# ET312.net
KiCad netlist of a schematic drawn in EAGLE
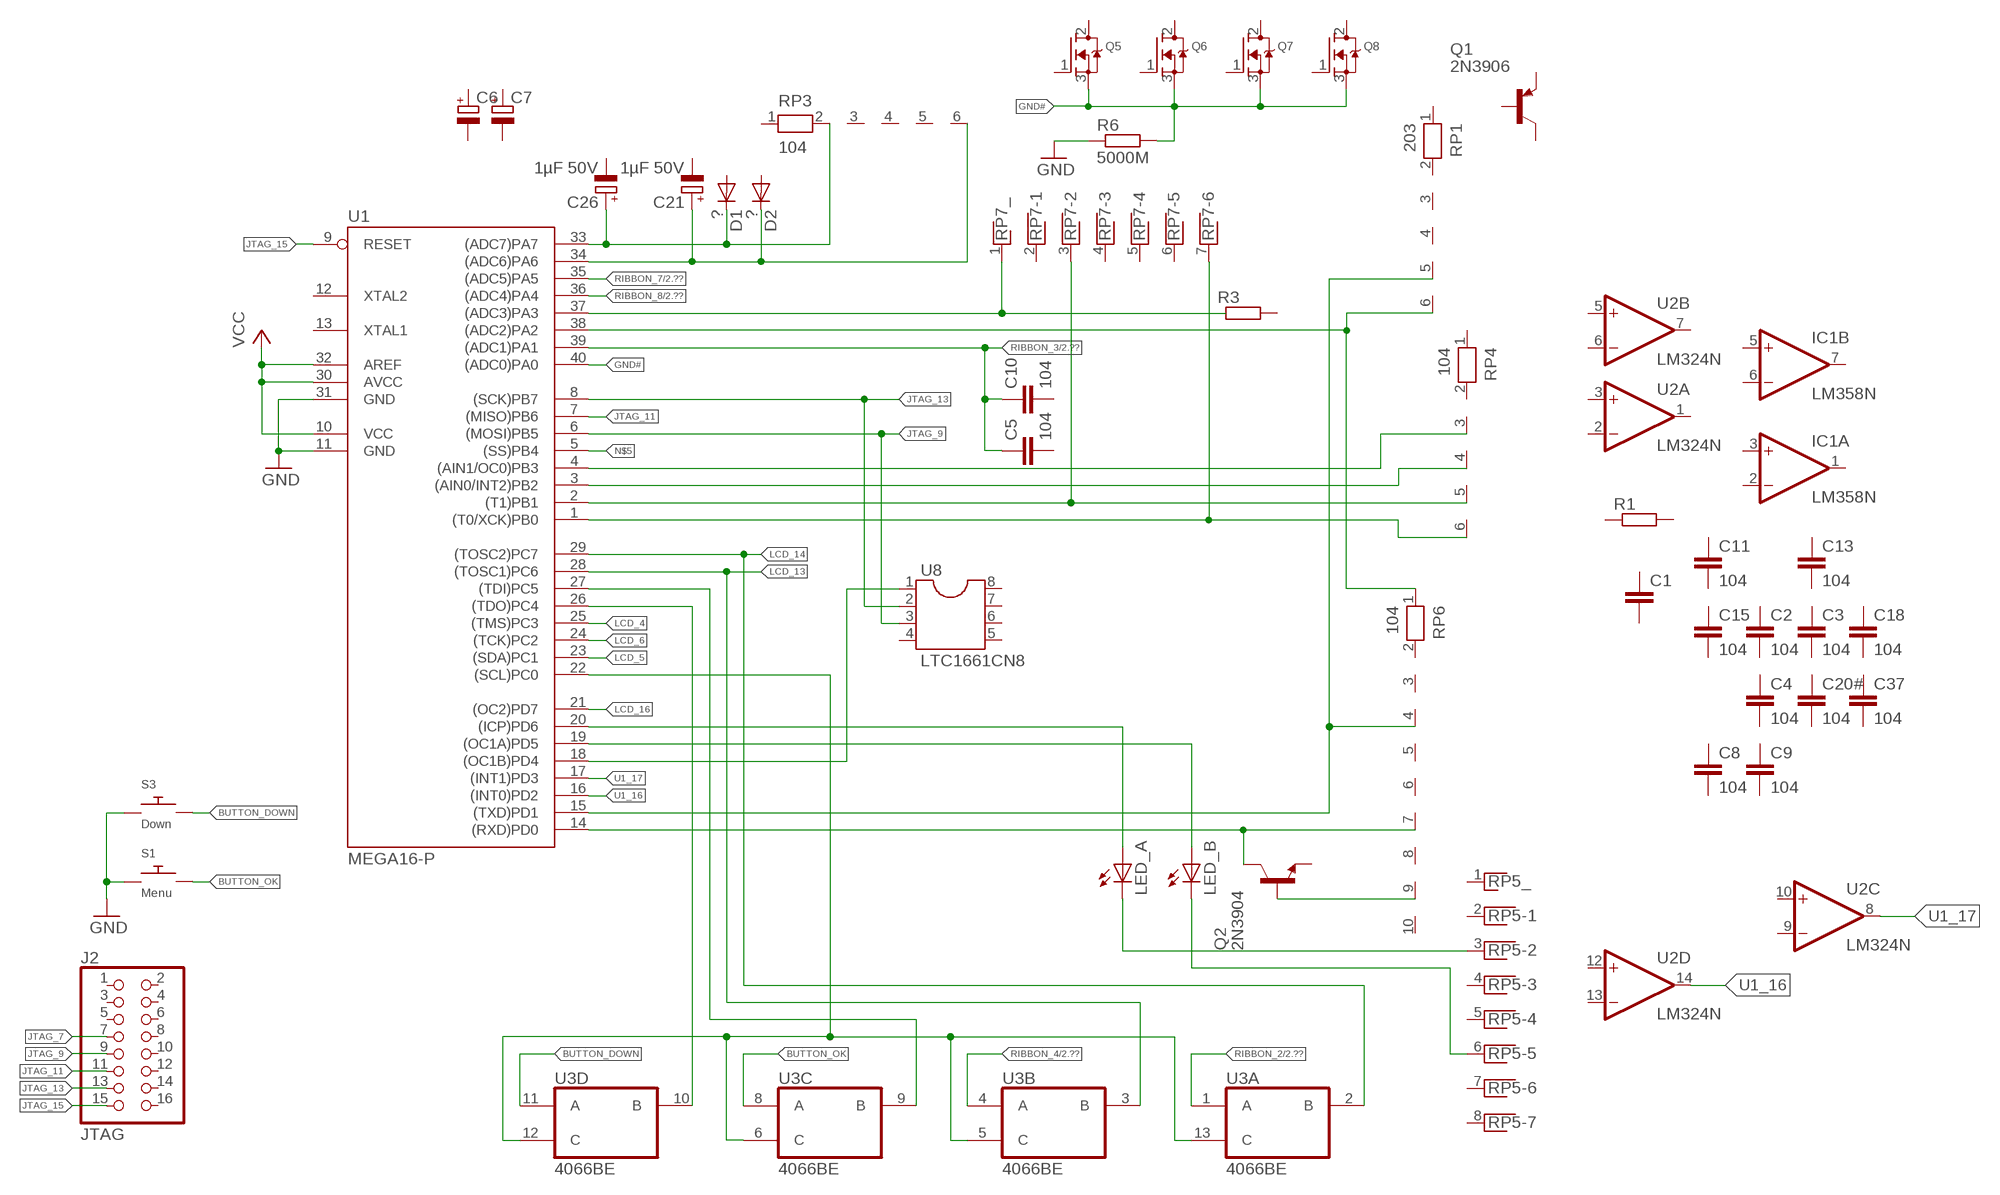
[diagram p0: schematic, sheet 1]
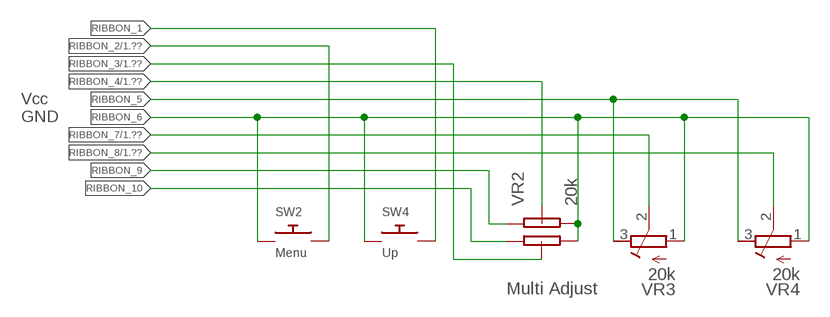
[diagram p1: schematic, sheet 2]

(export (version "E")
  (design (tool "Eeschema 10.0.6"))
  (components
    (comp (ref "SW2")
      (value "Menu")
      (footprint "eagle-import:TACT_PANA-EVQ")
      (libsource (lib "eagle-import") (part "SWITCH_PUSHBUTTONEVQ-PE"))
    )
    (comp (ref "SW4")
      (value "Up")
      (footprint "eagle-import:TACT_PANA-EVQ")
      (libsource (lib "eagle-import") (part "SWITCH_PUSHBUTTONEVQ-PE"))
    )
    (comp (ref "VR2")
      (value "20k")
      (footprint "eagle-import:EVJC")
      (libsource (lib "eagle-import") (part "EVJC"))
    )
    (comp (ref "VR3")
      (value "20k")
      (footprint "eagle-import:RTRIM64W")
      (libsource (lib "eagle-import") (part "R-TRIMM64W"))
    )
    (comp (ref "VR4")
      (value "20k")
      (footprint "eagle-import:RTRIM64W")
      (libsource (lib "eagle-import") (part "R-TRIMM64W"))
    )
    (comp (ref "C1")
      (value "C-EU025-025X050")
      (footprint "eagle-import:C025-025X050")
      (libsource (lib "eagle-import") (part "resistor_C-EU025-025X050"))
    )
    (comp (ref "C2")
      (value "104")
      (footprint "eagle-import:C025-024X044")
      (libsource (lib "eagle-import") (part "C-EU025-024X044"))
    )
    (comp (ref "C3")
      (value "104")
      (footprint "eagle-import:C025-024X044")
      (libsource (lib "eagle-import") (part "C-EU025-024X044"))
    )
    (comp (ref "C4")
      (value "104")
      (footprint "eagle-import:C025-024X044")
      (libsource (lib "eagle-import") (part "C-EU025-024X044"))
    )
    (comp (ref "C5")
      (value "104")
      (footprint "eagle-import:C025-024X044")
      (libsource (lib "eagle-import") (part "C-EU025-024X044"))
    )
    (comp (ref "C6")
      (value "CPOL-EUE2-5")
      (footprint "eagle-import:E2-5")
      (libsource (lib "eagle-import") (part "CPOL-EUE2-5"))
    )
    (comp (ref "C7")
      (value "CPOL-EUE2-5")
      (footprint "eagle-import:E2-5")
      (libsource (lib "eagle-import") (part "CPOL-EUE2-5"))
    )
    (comp (ref "C8")
      (value "104")
      (footprint "eagle-import:C025-024X044")
      (libsource (lib "eagle-import") (part "C-EU025-024X044"))
    )
    (comp (ref "C9")
      (value "104")
      (footprint "eagle-import:C025-024X044")
      (libsource (lib "eagle-import") (part "C-EU025-024X044"))
    )
    (comp (ref "C10")
      (value "104")
      (footprint "eagle-import:C025-024X044")
      (libsource (lib "eagle-import") (part "C-EU025-024X044"))
    )
    (comp (ref "C11")
      (value "104")
      (footprint "eagle-import:C025-024X044")
      (libsource (lib "eagle-import") (part "C-EU025-024X044"))
    )
    (comp (ref "C13")
      (value "104")
      (footprint "eagle-import:C025-024X044")
      (libsource (lib "eagle-import") (part "C-EU025-024X044"))
    )
    (comp (ref "C15")
      (value "104")
      (footprint "eagle-import:C025-024X044")
      (libsource (lib "eagle-import") (part "C-EU025-024X044"))
    )
    (comp (ref "C18")
      (value "104")
      (footprint "eagle-import:C025-024X044")
      (libsource (lib "eagle-import") (part "C-EU025-024X044"))
    )
    (comp (ref "C20#")
      (value "104")
      (footprint "eagle-import:C025-024X044")
      (libsource (lib "eagle-import") (part "C-EU025-024X044"))
    )
    (comp (ref "C21")
      (value "1µF 50V")
      (footprint "eagle-import:E2-5")
      (libsource (lib "eagle-import") (part "CPOL-EUE2-5"))
    )
    (comp (ref "C26")
      (value "1µF 50V")
      (footprint "eagle-import:E2-5")
      (libsource (lib "eagle-import") (part "CPOL-EUE2-5"))
    )
    (comp (ref "C37")
      (value "104")
      (footprint "eagle-import:C025-024X044")
      (libsource (lib "eagle-import") (part "C-EU025-024X044"))
    )
    (comp (ref "D1")
      (value "?")
      (footprint "eagle-import:DO41-10")
      (libsource (lib "eagle-import") (part "1N4004"))
    )
    (comp (ref "D2")
      (value "?")
      (footprint "eagle-import:DO41-10")
      (libsource (lib "eagle-import") (part "1N4004"))
    )
    (comp (ref "IC1")
      (value "LM358N")
      (footprint "eagle-import:DIL08")
      (libsource (lib "eagle-import") (part "LM358N"))
    )
    (comp (ref "J2")
      (value "JTAG")
      (footprint "eagle-import:2X08")
      (libsource (lib "eagle-import") (part "PINHD-2X8"))
    )
    (comp (ref "LED_A")
      (value "LEDB155")
      (footprint "eagle-import:Q62902-B155")
      (libsource (lib "eagle-import") (part "LEDB155"))
    )
    (comp (ref "LED_B")
      (value "LEDB155")
      (footprint "eagle-import:Q62902-B155")
      (libsource (lib "eagle-import") (part "LEDB155"))
    )
    (comp (ref "Q1")
      (value "2N3906")
      (footprint "eagle-import:TO92")
      (libsource (lib "eagle-import") (part "2N3906"))
    )
    (comp (ref "Q2")
      (value "2N3904")
      (footprint "eagle-import:TO92")
      (libsource (lib "eagle-import") (part "2N3904"))
    )
    (comp (ref "Q5")
      (value "MOSFET-NGDS_TO220V")
      (footprint "eagle-import:TO220V")
      (libsource (lib "eagle-import") (part "MOSFET-NGDS_TO220V"))
    )
    (comp (ref "Q6")
      (value "MOSFET-NGDS_TO220V")
      (footprint "eagle-import:TO220V")
      (libsource (lib "eagle-import") (part "MOSFET-NGDS_TO220V"))
    )
    (comp (ref "Q7")
      (value "MOSFET-NGDS_TO220V")
      (footprint "eagle-import:TO220V")
      (libsource (lib "eagle-import") (part "MOSFET-NGDS_TO220V"))
    )
    (comp (ref "Q8")
      (value "MOSFET-NGDS_TO220V")
      (footprint "eagle-import:TO220V")
      (libsource (lib "eagle-import") (part "MOSFET-NGDS_TO220V"))
    )
    (comp (ref "R1")
      (value "R-EU_0207/5V")
      (footprint "eagle-import:0207_5V")
      (libsource (lib "eagle-import") (part "R-EU_0207/5V"))
    )
    (comp (ref "R3")
      (value "R-EU_0207/5V")
      (footprint "eagle-import:0207_5V")
      (libsource (lib "eagle-import") (part "R-EU_0207/5V"))
    )
    (comp (ref "R6")
      (value "5000M")
      (footprint "eagle-import:0207_5V")
      (libsource (lib "eagle-import") (part "R-EU_0207/5V"))
    )
    (comp (ref "RP1")
      (value "203")
      (footprint "eagle-import:RN-6")
      (libsource (lib "eagle-import") (part "RN05"))
    )
    (comp (ref "RP3")
      (value "104")
      (footprint "eagle-import:RN-6")
      (libsource (lib "eagle-import") (part "RN05"))
    )
    (comp (ref "RP4")
      (value "104")
      (footprint "eagle-import:RN-6")
      (libsource (lib "eagle-import") (part "RN05"))
    )
    (comp (ref "RP5")
      (value "RNX7")
      (footprint "eagle-import:RN-8")
      (libsource (lib "eagle-import") (part "RNX7"))
    )
    (comp (ref "RP6")
      (value "104")
      (footprint "eagle-import:RN-10")
      (libsource (lib "eagle-import") (part "RN09"))
    )
    (comp (ref "RP7")
      (value "RNX6")
      (footprint "eagle-import:RN-7")
      (libsource (lib "eagle-import") (part "RNX6"))
    )
    (comp (ref "S1")
      (value "Menu")
      (footprint "eagle-import:TACT_PANA-EVQ")
      (libsource (lib "eagle-import") (part "SWITCH_PUSHBUTTONEVQ-PE"))
    )
    (comp (ref "S3")
      (value "Down")
      (footprint "eagle-import:TACT_PANA-EVQ")
      (libsource (lib "eagle-import") (part "SWITCH_PUSHBUTTONEVQ-PE"))
    )
    (comp (ref "U1")
      (value "MEGA16-P")
      (footprint "eagle-import:DIL40")
      (fields (field (name "MPN") "ATMEGA16-16PU"))
      (libsource (lib "eagle-import") (part "MEGA16-P"))
    )
    (comp (ref "U2")
      (value "LM324N")
      (footprint "eagle-import:DIL14")
      (libsource (lib "eagle-import") (part "LM324N"))
    )
    (comp (ref "U3")
      (value "4066BE")
      (footprint "eagle-import:DIL14")
      (libsource (lib "eagle-import") (part "4066N"))
    )
    (comp (ref "U8")
      (value "LTC1661CN8")
      (footprint "eagle-import:DIL08")
      (libsource (lib "eagle-import") (part "DIL8"))
    )
  )
  (nets
    (net (code "1") (name "BUTTON_DOWN") (class "Default")
      (node (ref "S3") (pin "P$2") (pinfunction "P$2_P$2") (pintype "passive"))
      (node (ref "U3") (pin "11") (pinfunction "A_11") (pintype "tri_state"))
    )
    (net (code "2") (name "BUTTON_OK") (class "Default")
      (node (ref "S1") (pin "P$2") (pinfunction "P$2_P$2") (pintype "passive"))
      (node (ref "U3") (pin "8") (pinfunction "A_8") (pintype "tri_state"))
    )
    (net (code "3") (name "GND") (class "Default")
      (node (ref "R6") (pin "1") (pinfunction "1_1") (pintype "passive"))
      (node (ref "S1") (pin "P$1") (pinfunction "P$1_P$1") (pintype "passive"))
      (node (ref "S3") (pin "P$1") (pinfunction "P$1_P$1") (pintype "passive"))
      (node (ref "U1") (pin "11") (pinfunction "GND_11") (pintype "power_in"))
      (node (ref "U1") (pin "31") (pinfunction "GND_31") (pintype "power_in"))
    )
    (net (code "4") (name "GND#") (class "Default")
      (node (ref "Q5") (pin "3") (pinfunction "S_3") (pintype "bidirectional"))
      (node (ref "Q6") (pin "3") (pinfunction "S_3") (pintype "bidirectional"))
      (node (ref "Q7") (pin "3") (pinfunction "S_3") (pintype "bidirectional"))
      (node (ref "Q8") (pin "3") (pinfunction "S_3") (pintype "bidirectional"))
      (node (ref "R6") (pin "2") (pinfunction "2_2") (pintype "passive"))
      (node (ref "U1") (pin "40") (pinfunction "(ADC0)PA0_40") (pintype "bidirectional"))
    )
    (net (code "5") (name "JTAG_7") (class "Default")
      (node (ref "J2") (pin "7") (pinfunction "7_7") (pintype "passive"))
      (node (ref "RP4") (pin "3") (pinfunction "3_3") (pintype "passive"))
      (node (ref "U1") (pin "4") (pinfunction "(AIN1/OC0)PB3_4") (pintype "bidirectional"))
    )
    (net (code "6") (name "JTAG_9") (class "Default")
      (node (ref "J2") (pin "9") (pinfunction "9_9") (pintype "passive"))
      (node (ref "U1") (pin "6") (pinfunction "(MOSI)PB5_6") (pintype "bidirectional"))
      (node (ref "U8") (pin "3") (pinfunction "3_3") (pintype "passive"))
    )
    (net (code "7") (name "JTAG_11") (class "Default")
      (node (ref "J2") (pin "11") (pinfunction "11_11") (pintype "passive"))
      (node (ref "U1") (pin "7") (pinfunction "(MISO)PB6_7") (pintype "bidirectional"))
    )
    (net (code "8") (name "JTAG_13") (class "Default")
      (node (ref "J2") (pin "13") (pinfunction "13_13") (pintype "passive"))
      (node (ref "U1") (pin "8") (pinfunction "(SCK)PB7_8") (pintype "bidirectional"))
      (node (ref "U8") (pin "2") (pinfunction "2_2") (pintype "passive"))
    )
    (net (code "9") (name "JTAG_15") (class "Default")
      (node (ref "J2") (pin "15") (pinfunction "15_15") (pintype "passive"))
      (node (ref "U1") (pin "9") (pinfunction "RESET_9") (pintype "input"))
    )
    (net (code "10") (name "LCD_4") (class "Default")
      (node (ref "U1") (pin "25") (pinfunction "(TMS)PC3_25") (pintype "bidirectional"))
    )
    (net (code "11") (name "LCD_5") (class "Default")
      (node (ref "U1") (pin "23") (pinfunction "(SDA)PC1_23") (pintype "bidirectional"))
    )
    (net (code "12") (name "LCD_6") (class "Default")
      (node (ref "U1") (pin "24") (pinfunction "(TCK)PC2_24") (pintype "bidirectional"))
    )
    (net (code "13") (name "LCD_13") (class "Default")
      (node (ref "U1") (pin "28") (pinfunction "(TOSC1)PC6_28") (pintype "bidirectional"))
      (node (ref "U3") (pin "3") (pinfunction "B_3") (pintype "tri_state"))
    )
    (net (code "14") (name "LCD_14") (class "Default")
      (node (ref "U1") (pin "29") (pinfunction "(TOSC2)PC7_29") (pintype "bidirectional"))
      (node (ref "U3") (pin "2") (pinfunction "B_2") (pintype "tri_state"))
    )
    (net (code "15") (name "LCD_16") (class "Default")
      (node (ref "U1") (pin "21") (pinfunction "(OC2)PD7_21") (pintype "bidirectional"))
    )
    (net (code "16") (name "N$5") (class "Default")
      (node (ref "U1") (pin "5") (pinfunction "(SS)PB4_5") (pintype "bidirectional"))
    )
    (net (code "17") (name "Net-(LED_A-C)") (class "Default")
      (node (ref "LED_A") (pin "K") (pinfunction "C_K") (pintype "passive"))
      (node (ref "RP5") (pin "3") (pinfunction "1_3") (pintype "passive"))
    )
    (net (code "18") (name "Net-(LED_B-C)") (class "Default")
      (node (ref "LED_B") (pin "K") (pinfunction "C_K") (pintype "passive"))
      (node (ref "RP5") (pin "6") (pinfunction "1_6") (pintype "passive"))
    )
    (net (code "19") (name "Net-(Q2-B)") (class "Default")
      (node (ref "Q2") (pin "2") (pinfunction "B_2") (pintype "passive"))
      (node (ref "RP6") (pin "9") (pinfunction "9_9") (pintype "passive"))
    )
    (net (code "20") (name "Net-(Q2-C)") (class "Default")
      (node (ref "Q2") (pin "1") (pinfunction "C_1") (pintype "passive"))
      (node (ref "RP6") (pin "7") (pinfunction "7_7") (pintype "passive"))
      (node (ref "U1") (pin "14") (pinfunction "(RXD)PD0_14") (pintype "bidirectional"))
    )
    (net (code "21") (name "Net-(RP7B-1)") (class "Default")
      (node (ref "RP4") (pin "5") (pinfunction "5_5") (pintype "passive"))
      (node (ref "RP7") (pin "3") (pinfunction "1_3") (pintype "passive"))
      (node (ref "U1") (pin "2") (pinfunction "(T1)PB1_2") (pintype "bidirectional"))
    )
    (net (code "22") (name "Net-(RP7F-1)") (class "Default")
      (node (ref "RP4") (pin "6") (pinfunction "6_6") (pintype "passive"))
      (node (ref "RP7") (pin "7") (pinfunction "1_7") (pintype "passive"))
      (node (ref "U1") (pin "1") (pinfunction "(T0/XCK)PB0_1") (pintype "bidirectional"))
    )
    (net (code "23") (name "Net-(U1-(ADC2)PA2)") (class "Default")
      (node (ref "RP1") (pin "6") (pinfunction "6_6") (pintype "passive"))
      (node (ref "RP6") (pin "1") (pinfunction "1_1") (pintype "passive"))
      (node (ref "U1") (pin "38") (pinfunction "(ADC2)PA2_38") (pintype "bidirectional"))
    )
    (net (code "24") (name "Net-(U1-(ADC3)PA3)") (class "Default")
      (node (ref "R3") (pin "1") (pinfunction "1_1") (pintype "passive"))
      (node (ref "RP7") (pin "1") (pinfunction "1_1") (pintype "passive"))
      (node (ref "U1") (pin "37") (pinfunction "(ADC3)PA3_37") (pintype "bidirectional"))
    )
    (net (code "25") (name "Net-(U1-(ADC6)PA6)") (class "Default")
      (node (ref "C21") (pin "+") (pinfunction "+_+") (pintype "passive"))
      (node (ref "D2") (pin "C") (pinfunction "C_C") (pintype "passive"))
      (node (ref "RP3") (pin "6") (pinfunction "6_6") (pintype "passive"))
      (node (ref "U1") (pin "34") (pinfunction "(ADC6)PA6_34") (pintype "bidirectional"))
    )
    (net (code "26") (name "Net-(U1-(ADC7)PA7)") (class "Default")
      (node (ref "C26") (pin "+") (pinfunction "+_+") (pintype "passive"))
      (node (ref "D1") (pin "C") (pinfunction "C_C") (pintype "passive"))
      (node (ref "RP3") (pin "2") (pinfunction "2_2") (pintype "passive"))
      (node (ref "U1") (pin "33") (pinfunction "(ADC7)PA7_33") (pintype "bidirectional"))
    )
    (net (code "27") (name "Net-(U1-(AIN0{slash}INT2)PB2)") (class "Default")
      (node (ref "RP4") (pin "4") (pinfunction "4_4") (pintype "passive"))
      (node (ref "U1") (pin "3") (pinfunction "(AIN0/INT2)PB2_3") (pintype "bidirectional"))
    )
    (net (code "28") (name "Net-(U1-(ICP)PD6)") (class "Default")
      (node (ref "LED_A") (pin "A") (pinfunction "A_A") (pintype "passive"))
      (node (ref "U1") (pin "20") (pinfunction "(ICP)PD6_20") (pintype "bidirectional"))
    )
    (net (code "29") (name "Net-(U1-(OC1A)PD5)") (class "Default")
      (node (ref "LED_B") (pin "A") (pinfunction "A_A") (pintype "passive"))
      (node (ref "U1") (pin "19") (pinfunction "(OC1A)PD5_19") (pintype "bidirectional"))
    )
    (net (code "30") (name "Net-(U1-(OC1B)PD4)") (class "Default")
      (node (ref "U1") (pin "18") (pinfunction "(OC1B)PD4_18") (pintype "bidirectional"))
      (node (ref "U8") (pin "1") (pinfunction "1_1") (pintype "passive"))
    )
    (net (code "31") (name "Net-(U1-(TDI)PC5)") (class "Default")
      (node (ref "U1") (pin "27") (pinfunction "(TDI)PC5_27") (pintype "bidirectional"))
      (node (ref "U3") (pin "9") (pinfunction "B_9") (pintype "tri_state"))
    )
    (net (code "32") (name "Net-(U1-(TDO)PC4)") (class "Default")
      (node (ref "U1") (pin "26") (pinfunction "(TDO)PC4_26") (pintype "bidirectional"))
      (node (ref "U3") (pin "10") (pinfunction "B_10") (pintype "tri_state"))
    )
    (net (code "33") (name "Net-(U1-(TXD)PD1)") (class "Default")
      (node (ref "RP1") (pin "5") (pinfunction "5_5") (pintype "passive"))
      (node (ref "RP6") (pin "4") (pinfunction "4_4") (pintype "passive"))
      (node (ref "U1") (pin "15") (pinfunction "(TXD)PD1_15") (pintype "bidirectional"))
    )
    (net (code "34") (name "RIBBON_1") (class "Default")
      (node (ref "SW4") (pin "P$2") (pinfunction "P$2_P$2") (pintype "passive"))
    )
    (net (code "35") (name "RIBBON_2") (class "Default")
      (node (ref "SW2") (pin "P$2") (pinfunction "P$2_P$2") (pintype "passive"))
      (node (ref "U3") (pin "1") (pinfunction "A_1") (pintype "tri_state"))
    )
    (net (code "36") (name "RIBBON_3") (class "Default")
      (node (ref "C10") (pin "1") (pinfunction "1_1") (pintype "passive"))
      (node (ref "C5") (pin "1") (pinfunction "1_1") (pintype "passive"))
      (node (ref "U1") (pin "39") (pinfunction "(ADC1)PA1_39") (pintype "bidirectional"))
      (node (ref "VR2") (pin "I2") (pinfunction "I2_I2") (pintype "output"))
    )
    (net (code "37") (name "RIBBON_4") (class "Default")
      (node (ref "U1") (pin "22") (pinfunction "(SCL)PC0_22") (pintype "bidirectional"))
      (node (ref "U3") (pin "12") (pinfunction "C_12") (pintype "input"))
      (node (ref "U3") (pin "13") (pinfunction "C_13") (pintype "input"))
      (node (ref "U3") (pin "4") (pinfunction "A_4") (pintype "tri_state"))
      (node (ref "U3") (pin "5") (pinfunction "C_5") (pintype "input"))
      (node (ref "U3") (pin "6") (pinfunction "C_6") (pintype "input"))
      (node (ref "VR2") (pin "II2") (pinfunction "II2_II2") (pintype "output"))
    )
    (net (code "38") (name "RIBBON_5") (class "Default")
      (node (ref "VR3") (pin "3") (pinfunction "E_3") (pintype "passive"))
      (node (ref "VR4") (pin "3") (pinfunction "E_3") (pintype "passive"))
    )
    (net (code "39") (name "RIBBON_6") (class "Default")
      (node (ref "SW2") (pin "P$1") (pinfunction "P$1_P$1") (pintype "passive"))
      (node (ref "SW4") (pin "P$1") (pinfunction "P$1_P$1") (pintype "passive"))
      (node (ref "VR2") (pin "I1") (pinfunction "I1_I1") (pintype "input"))
      (node (ref "VR2") (pin "II1") (pinfunction "II1_II1") (pintype "input"))
      (node (ref "VR3") (pin "1") (pinfunction "A_1") (pintype "passive"))
      (node (ref "VR4") (pin "1") (pinfunction "A_1") (pintype "passive"))
    )
    (net (code "40") (name "RIBBON_7") (class "Default")
      (node (ref "U1") (pin "35") (pinfunction "(ADC5)PA5_35") (pintype "bidirectional"))
      (node (ref "VR3") (pin "2") (pinfunction "S_2") (pintype "passive"))
    )
    (net (code "41") (name "RIBBON_8") (class "Default")
      (node (ref "U1") (pin "36") (pinfunction "(ADC4)PA4_36") (pintype "bidirectional"))
      (node (ref "VR4") (pin "2") (pinfunction "S_2") (pintype "passive"))
    )
    (net (code "42") (name "RIBBON_9") (class "Default")
      (node (ref "VR2") (pin "II3") (pinfunction "II3_II3") (pintype "input"))
    )
    (net (code "43") (name "RIBBON_10") (class "Default")
      (node (ref "VR2") (pin "I3") (pinfunction "I3_I3") (pintype "input"))
    )
    (net (code "44") (name "U1_16") (class "Default")
      (node (ref "U1") (pin "16") (pinfunction "(INT0)PD2_16") (pintype "bidirectional"))
      (node (ref "U2") (pin "14") (pinfunction "OUT_14") (pintype "output"))
    )
    (net (code "45") (name "U1_17") (class "Default")
      (node (ref "U1") (pin "17") (pinfunction "(INT1)PD3_17") (pintype "bidirectional"))
      (node (ref "U2") (pin "8") (pinfunction "OUT_8") (pintype "output"))
    )
    (net (code "46") (name "VCC") (class "Default")
      (node (ref "U1") (pin "10") (pinfunction "VCC_10") (pintype "power_in"))
      (node (ref "U1") (pin "30") (pinfunction "AVCC_30") (pintype "power_in"))
      (node (ref "U1") (pin "32") (pinfunction "AREF_32") (pintype "passive"))
    )
    (net (code "47") (name "unconnected-(C1-Pad1)") (class "Default")
      (node (ref "C1") (pin "1") (pinfunction "1_1") (pintype "passive"))
    )
    (net (code "48") (name "unconnected-(C1-Pad2)") (class "Default")
      (node (ref "C1") (pin "2") (pinfunction "2_2") (pintype "passive"))
    )
    (net (code "49") (name "unconnected-(C2-Pad1)") (class "Default")
      (node (ref "C2") (pin "1") (pinfunction "1_1") (pintype "passive"))
    )
    (net (code "50") (name "unconnected-(C2-Pad2)") (class "Default")
      (node (ref "C2") (pin "2") (pinfunction "2_2") (pintype "passive"))
    )
    (net (code "51") (name "unconnected-(C3-Pad1)") (class "Default")
      (node (ref "C3") (pin "1") (pinfunction "1_1") (pintype "passive"))
    )
    (net (code "52") (name "unconnected-(C3-Pad2)") (class "Default")
      (node (ref "C3") (pin "2") (pinfunction "2_2") (pintype "passive"))
    )
    (net (code "53") (name "unconnected-(C4-Pad1)") (class "Default")
      (node (ref "C4") (pin "1") (pinfunction "1_1") (pintype "passive"))
    )
    (net (code "54") (name "unconnected-(C4-Pad2)") (class "Default")
      (node (ref "C4") (pin "2") (pinfunction "2_2") (pintype "passive"))
    )
    (net (code "55") (name "unconnected-(C5-Pad2)") (class "Default")
      (node (ref "C5") (pin "2") (pinfunction "2_2") (pintype "passive"))
    )
    (net (code "56") (name "unconnected-(C6-Pad+)") (class "Default")
      (node (ref "C6") (pin "+") (pinfunction "+_+") (pintype "passive"))
    )
    (net (code "57") (name "unconnected-(C6-Pad-)") (class "Default")
      (node (ref "C6") (pin "-") (pinfunction "-_-") (pintype "passive"))
    )
    (net (code "58") (name "unconnected-(C7-Pad+)") (class "Default")
      (node (ref "C7") (pin "+") (pinfunction "+_+") (pintype "passive"))
    )
    (net (code "59") (name "unconnected-(C7-Pad-)") (class "Default")
      (node (ref "C7") (pin "-") (pinfunction "-_-") (pintype "passive"))
    )
    (net (code "60") (name "unconnected-(C8-Pad1)") (class "Default")
      (node (ref "C8") (pin "1") (pinfunction "1_1") (pintype "passive"))
    )
    (net (code "61") (name "unconnected-(C8-Pad2)") (class "Default")
      (node (ref "C8") (pin "2") (pinfunction "2_2") (pintype "passive"))
    )
    (net (code "62") (name "unconnected-(C9-Pad1)") (class "Default")
      (node (ref "C9") (pin "1") (pinfunction "1_1") (pintype "passive"))
    )
    (net (code "63") (name "unconnected-(C9-Pad2)") (class "Default")
      (node (ref "C9") (pin "2") (pinfunction "2_2") (pintype "passive"))
    )
    (net (code "64") (name "unconnected-(C10-Pad2)") (class "Default")
      (node (ref "C10") (pin "2") (pinfunction "2_2") (pintype "passive"))
    )
    (net (code "65") (name "unconnected-(C11-Pad1)") (class "Default")
      (node (ref "C11") (pin "1") (pinfunction "1_1") (pintype "passive"))
    )
    (net (code "66") (name "unconnected-(C11-Pad2)") (class "Default")
      (node (ref "C11") (pin "2") (pinfunction "2_2") (pintype "passive"))
    )
    (net (code "67") (name "unconnected-(C13-Pad1)") (class "Default")
      (node (ref "C13") (pin "1") (pinfunction "1_1") (pintype "passive"))
    )
    (net (code "68") (name "unconnected-(C13-Pad2)") (class "Default")
      (node (ref "C13") (pin "2") (pinfunction "2_2") (pintype "passive"))
    )
    (net (code "69") (name "unconnected-(C15-Pad1)") (class "Default")
      (node (ref "C15") (pin "1") (pinfunction "1_1") (pintype "passive"))
    )
    (net (code "70") (name "unconnected-(C15-Pad2)") (class "Default")
      (node (ref "C15") (pin "2") (pinfunction "2_2") (pintype "passive"))
    )
    (net (code "71") (name "unconnected-(C18-Pad1)") (class "Default")
      (node (ref "C18") (pin "1") (pinfunction "1_1") (pintype "passive"))
    )
    (net (code "72") (name "unconnected-(C18-Pad2)") (class "Default")
      (node (ref "C18") (pin "2") (pinfunction "2_2") (pintype "passive"))
    )
    (net (code "73") (name "unconnected-(C20#-Pad1)") (class "Default")
      (node (ref "C20#") (pin "1") (pinfunction "1_1") (pintype "passive"))
    )
    (net (code "74") (name "unconnected-(C20#-Pad2)") (class "Default")
      (node (ref "C20#") (pin "2") (pinfunction "2_2") (pintype "passive"))
    )
    (net (code "75") (name "unconnected-(C21-Pad-)") (class "Default")
      (node (ref "C21") (pin "-") (pinfunction "-_-") (pintype "passive"))
    )
    (net (code "76") (name "unconnected-(C26-Pad-)") (class "Default")
      (node (ref "C26") (pin "-") (pinfunction "-_-") (pintype "passive"))
    )
    (net (code "77") (name "unconnected-(C37-Pad1)") (class "Default")
      (node (ref "C37") (pin "1") (pinfunction "1_1") (pintype "passive"))
    )
    (net (code "78") (name "unconnected-(C37-Pad2)") (class "Default")
      (node (ref "C37") (pin "2") (pinfunction "2_2") (pintype "passive"))
    )
    (net (code "79") (name "unconnected-(D1-PadA)") (class "Default")
      (node (ref "D1") (pin "A") (pinfunction "A_A") (pintype "passive"))
    )
    (net (code "80") (name "unconnected-(D2-PadA)") (class "Default")
      (node (ref "D2") (pin "A") (pinfunction "A_A") (pintype "passive"))
    )
    (net (code "81") (name "unconnected-(IC1A-+IN-Pad3)") (class "Default")
      (node (ref "IC1") (pin "3") (pinfunction "+IN_3") (pintype "input"))
    )
    (net (code "82") (name "unconnected-(IC1A--IN-Pad2)") (class "Default")
      (node (ref "IC1") (pin "2") (pinfunction "-IN_2") (pintype "input"))
    )
    (net (code "83") (name "unconnected-(IC1A-OUT-Pad1)") (class "Default")
      (node (ref "IC1") (pin "1") (pinfunction "OUT_1") (pintype "output"))
    )
    (net (code "84") (name "unconnected-(IC1B-+IN-Pad5)") (class "Default")
      (node (ref "IC1") (pin "5") (pinfunction "+IN_5") (pintype "input"))
    )
    (net (code "85") (name "unconnected-(IC1B--IN-Pad6)") (class "Default")
      (node (ref "IC1") (pin "6") (pinfunction "-IN_6") (pintype "input"))
    )
    (net (code "86") (name "unconnected-(IC1B-OUT-Pad7)") (class "Default")
      (node (ref "IC1") (pin "7") (pinfunction "OUT_7") (pintype "output"))
    )
    (net (code "87") (name "unconnected-(J2-Pad1)") (class "Default")
      (node (ref "J2") (pin "1") (pinfunction "1_1") (pintype "passive"))
    )
    (net (code "88") (name "unconnected-(J2-Pad2)") (class "Default")
      (node (ref "J2") (pin "2") (pinfunction "2_2") (pintype "passive"))
    )
    (net (code "89") (name "unconnected-(J2-Pad3)") (class "Default")
      (node (ref "J2") (pin "3") (pinfunction "3_3") (pintype "passive"))
    )
    (net (code "90") (name "unconnected-(J2-Pad4)") (class "Default")
      (node (ref "J2") (pin "4") (pinfunction "4_4") (pintype "passive"))
    )
    (net (code "91") (name "unconnected-(J2-Pad5)") (class "Default")
      (node (ref "J2") (pin "5") (pinfunction "5_5") (pintype "passive"))
    )
    (net (code "92") (name "unconnected-(J2-Pad6)") (class "Default")
      (node (ref "J2") (pin "6") (pinfunction "6_6") (pintype "passive"))
    )
    (net (code "93") (name "unconnected-(J2-Pad8)") (class "Default")
      (node (ref "J2") (pin "8") (pinfunction "8_8") (pintype "passive"))
    )
    (net (code "94") (name "unconnected-(J2-Pad10)") (class "Default")
      (node (ref "J2") (pin "10") (pinfunction "10_10") (pintype "passive"))
    )
    (net (code "95") (name "unconnected-(J2-Pad12)") (class "Default")
      (node (ref "J2") (pin "12") (pinfunction "12_12") (pintype "passive"))
    )
    (net (code "96") (name "unconnected-(J2-Pad14)") (class "Default")
      (node (ref "J2") (pin "14") (pinfunction "14_14") (pintype "passive"))
    )
    (net (code "97") (name "unconnected-(J2-Pad16)") (class "Default")
      (node (ref "J2") (pin "16") (pinfunction "16_16") (pintype "passive"))
    )
    (net (code "98") (name "unconnected-(Q1-B-Pad2)") (class "Default")
      (node (ref "Q1") (pin "2") (pinfunction "B_2") (pintype "passive"))
    )
    (net (code "99") (name "unconnected-(Q1-C-Pad1)") (class "Default")
      (node (ref "Q1") (pin "1") (pinfunction "C_1") (pintype "passive"))
    )
    (net (code "100") (name "unconnected-(Q1-E-Pad3)") (class "Default")
      (node (ref "Q1") (pin "3") (pinfunction "E_3") (pintype "passive"))
    )
    (net (code "101") (name "unconnected-(Q2-E-Pad3)") (class "Default")
      (node (ref "Q2") (pin "3") (pinfunction "E_3") (pintype "passive"))
    )
    (net (code "102") (name "unconnected-(Q5-D-Pad2)") (class "Default")
      (node (ref "Q5") (pin "2") (pinfunction "D_2") (pintype "bidirectional"))
    )
    (net (code "103") (name "unconnected-(Q5-G-Pad1)") (class "Default")
      (node (ref "Q5") (pin "1") (pinfunction "G_1") (pintype "bidirectional"))
    )
    (net (code "104") (name "unconnected-(Q6-D-Pad2)") (class "Default")
      (node (ref "Q6") (pin "2") (pinfunction "D_2") (pintype "bidirectional"))
    )
    (net (code "105") (name "unconnected-(Q6-G-Pad1)") (class "Default")
      (node (ref "Q6") (pin "1") (pinfunction "G_1") (pintype "bidirectional"))
    )
    (net (code "106") (name "unconnected-(Q7-D-Pad2)") (class "Default")
      (node (ref "Q7") (pin "2") (pinfunction "D_2") (pintype "bidirectional"))
    )
    (net (code "107") (name "unconnected-(Q7-G-Pad1)") (class "Default")
      (node (ref "Q7") (pin "1") (pinfunction "G_1") (pintype "bidirectional"))
    )
    (net (code "108") (name "unconnected-(Q8-D-Pad2)") (class "Default")
      (node (ref "Q8") (pin "2") (pinfunction "D_2") (pintype "bidirectional"))
    )
    (net (code "109") (name "unconnected-(Q8-G-Pad1)") (class "Default")
      (node (ref "Q8") (pin "1") (pinfunction "G_1") (pintype "bidirectional"))
    )
    (net (code "110") (name "unconnected-(R1-Pad1)") (class "Default")
      (node (ref "R1") (pin "1") (pinfunction "1_1") (pintype "passive"))
    )
    (net (code "111") (name "unconnected-(R1-Pad2)") (class "Default")
      (node (ref "R1") (pin "2") (pinfunction "2_2") (pintype "passive"))
    )
    (net (code "112") (name "unconnected-(R3-Pad2)") (class "Default")
      (node (ref "R3") (pin "2") (pinfunction "2_2") (pintype "passive"))
    )
    (net (code "113") (name "unconnected-(RP1-Pad1)") (class "Default")
      (node (ref "RP1") (pin "1") (pinfunction "1_1") (pintype "passive"))
    )
    (net (code "114") (name "unconnected-(RP1-Pad2)") (class "Default")
      (node (ref "RP1") (pin "2") (pinfunction "2_2") (pintype "passive"))
    )
    (net (code "115") (name "unconnected-(RP1-Pad3)") (class "Default")
      (node (ref "RP1") (pin "3") (pinfunction "3_3") (pintype "passive"))
    )
    (net (code "116") (name "unconnected-(RP1-Pad4)") (class "Default")
      (node (ref "RP1") (pin "4") (pinfunction "4_4") (pintype "passive"))
    )
    (net (code "117") (name "unconnected-(RP3-Pad1)") (class "Default")
      (node (ref "RP3") (pin "1") (pinfunction "1_1") (pintype "passive"))
    )
    (net (code "118") (name "unconnected-(RP3-Pad3)") (class "Default")
      (node (ref "RP3") (pin "3") (pinfunction "3_3") (pintype "passive"))
    )
    (net (code "119") (name "unconnected-(RP3-Pad4)") (class "Default")
      (node (ref "RP3") (pin "4") (pinfunction "4_4") (pintype "passive"))
    )
    (net (code "120") (name "unconnected-(RP3-Pad5)") (class "Default")
      (node (ref "RP3") (pin "5") (pinfunction "5_5") (pintype "passive"))
    )
    (net (code "121") (name "unconnected-(RP4-Pad1)") (class "Default")
      (node (ref "RP4") (pin "1") (pinfunction "1_1") (pintype "passive"))
    )
    (net (code "122") (name "unconnected-(RP4-Pad2)") (class "Default")
      (node (ref "RP4") (pin "2") (pinfunction "2_2") (pintype "passive"))
    )
    (net (code "123") (name "unconnected-(RP5-Pad1)") (class "Default")
      (node (ref "RP5") (pin "1") (pinfunction "1_1") (pintype "passive"))
    )
    (net (code "124") (name "unconnected-(RP5A-1-Pad2)") (class "Default")
      (node (ref "RP5") (pin "2") (pinfunction "1_2") (pintype "passive"))
    )
    (net (code "125") (name "unconnected-(RP5C-1-Pad4)") (class "Default")
      (node (ref "RP5") (pin "4") (pinfunction "1_4") (pintype "passive"))
    )
    (net (code "126") (name "unconnected-(RP5D-1-Pad5)") (class "Default")
      (node (ref "RP5") (pin "5") (pinfunction "1_5") (pintype "passive"))
    )
    (net (code "127") (name "unconnected-(RP5F-1-Pad7)") (class "Default")
      (node (ref "RP5") (pin "7") (pinfunction "1_7") (pintype "passive"))
    )
    (net (code "128") (name "unconnected-(RP5G-1-Pad8)") (class "Default")
      (node (ref "RP5") (pin "8") (pinfunction "1_8") (pintype "passive"))
    )
    (net (code "129") (name "unconnected-(RP6-Pad2)") (class "Default")
      (node (ref "RP6") (pin "2") (pinfunction "2_2") (pintype "passive"))
    )
    (net (code "130") (name "unconnected-(RP6-Pad3)") (class "Default")
      (node (ref "RP6") (pin "3") (pinfunction "3_3") (pintype "passive"))
    )
    (net (code "131") (name "unconnected-(RP6-Pad5)") (class "Default")
      (node (ref "RP6") (pin "5") (pinfunction "5_5") (pintype "passive"))
    )
    (net (code "132") (name "unconnected-(RP6-Pad6)") (class "Default")
      (node (ref "RP6") (pin "6") (pinfunction "6_6") (pintype "passive"))
    )
    (net (code "133") (name "unconnected-(RP6-Pad8)") (class "Default")
      (node (ref "RP6") (pin "8") (pinfunction "8_8") (pintype "passive"))
    )
    (net (code "134") (name "unconnected-(RP6-Pad10)") (class "Default")
      (node (ref "RP6") (pin "10") (pinfunction "10_10") (pintype "passive"))
    )
    (net (code "135") (name "unconnected-(RP7A-1-Pad2)") (class "Default")
      (node (ref "RP7") (pin "2") (pinfunction "1_2") (pintype "passive"))
    )
    (net (code "136") (name "unconnected-(RP7C-1-Pad4)") (class "Default")
      (node (ref "RP7") (pin "4") (pinfunction "1_4") (pintype "passive"))
    )
    (net (code "137") (name "unconnected-(RP7D-1-Pad5)") (class "Default")
      (node (ref "RP7") (pin "5") (pinfunction "1_5") (pintype "passive"))
    )
    (net (code "138") (name "unconnected-(RP7E-1-Pad6)") (class "Default")
      (node (ref "RP7") (pin "6") (pinfunction "1_6") (pintype "passive"))
    )
    (net (code "139") (name "unconnected-(U1-XTAL1-Pad13)") (class "Default")
      (node (ref "U1") (pin "13") (pinfunction "XTAL1_13") (pintype "bidirectional"))
    )
    (net (code "140") (name "unconnected-(U1-XTAL2-Pad12)") (class "Default")
      (node (ref "U1") (pin "12") (pinfunction "XTAL2_12") (pintype "bidirectional"))
    )
    (net (code "141") (name "unconnected-(U2A-+IN-Pad3)") (class "Default")
      (node (ref "U2") (pin "3") (pinfunction "+IN_3") (pintype "input"))
    )
    (net (code "142") (name "unconnected-(U2A--IN-Pad2)") (class "Default")
      (node (ref "U2") (pin "2") (pinfunction "-IN_2") (pintype "input"))
    )
    (net (code "143") (name "unconnected-(U2A-OUT-Pad1)") (class "Default")
      (node (ref "U2") (pin "1") (pinfunction "OUT_1") (pintype "output"))
    )
    (net (code "144") (name "unconnected-(U2B-+IN-Pad5)") (class "Default")
      (node (ref "U2") (pin "5") (pinfunction "+IN_5") (pintype "input"))
    )
    (net (code "145") (name "unconnected-(U2B--IN-Pad6)") (class "Default")
      (node (ref "U2") (pin "6") (pinfunction "-IN_6") (pintype "input"))
    )
    (net (code "146") (name "unconnected-(U2B-OUT-Pad7)") (class "Default")
      (node (ref "U2") (pin "7") (pinfunction "OUT_7") (pintype "output"))
    )
    (net (code "147") (name "unconnected-(U2C-+IN-Pad10)") (class "Default")
      (node (ref "U2") (pin "10") (pinfunction "+IN_10") (pintype "input"))
    )
    (net (code "148") (name "unconnected-(U2C--IN-Pad9)") (class "Default")
      (node (ref "U2") (pin "9") (pinfunction "-IN_9") (pintype "input"))
    )
    (net (code "149") (name "unconnected-(U2D-+IN-Pad12)") (class "Default")
      (node (ref "U2") (pin "12") (pinfunction "+IN_12") (pintype "input"))
    )
    (net (code "150") (name "unconnected-(U2D--IN-Pad13)") (class "Default")
      (node (ref "U2") (pin "13") (pinfunction "-IN_13") (pintype "input"))
    )
    (net (code "151") (name "unconnected-(U8-Pad4)") (class "Default")
      (node (ref "U8") (pin "4") (pinfunction "4_4") (pintype "passive"))
    )
    (net (code "152") (name "unconnected-(U8-Pad5)") (class "Default")
      (node (ref "U8") (pin "5") (pinfunction "5_5") (pintype "passive"))
    )
    (net (code "153") (name "unconnected-(U8-Pad6)") (class "Default")
      (node (ref "U8") (pin "6") (pinfunction "6_6") (pintype "passive"))
    )
    (net (code "154") (name "unconnected-(U8-Pad7)") (class "Default")
      (node (ref "U8") (pin "7") (pinfunction "7_7") (pintype "passive"))
    )
    (net (code "155") (name "unconnected-(U8-Pad8)") (class "Default")
      (node (ref "U8") (pin "8") (pinfunction "8_8") (pintype "passive"))
    )
  )
)
